# DRV8701E_V1_0.net
KiCad netlist of a schematic drawn in EasyEDA Pro
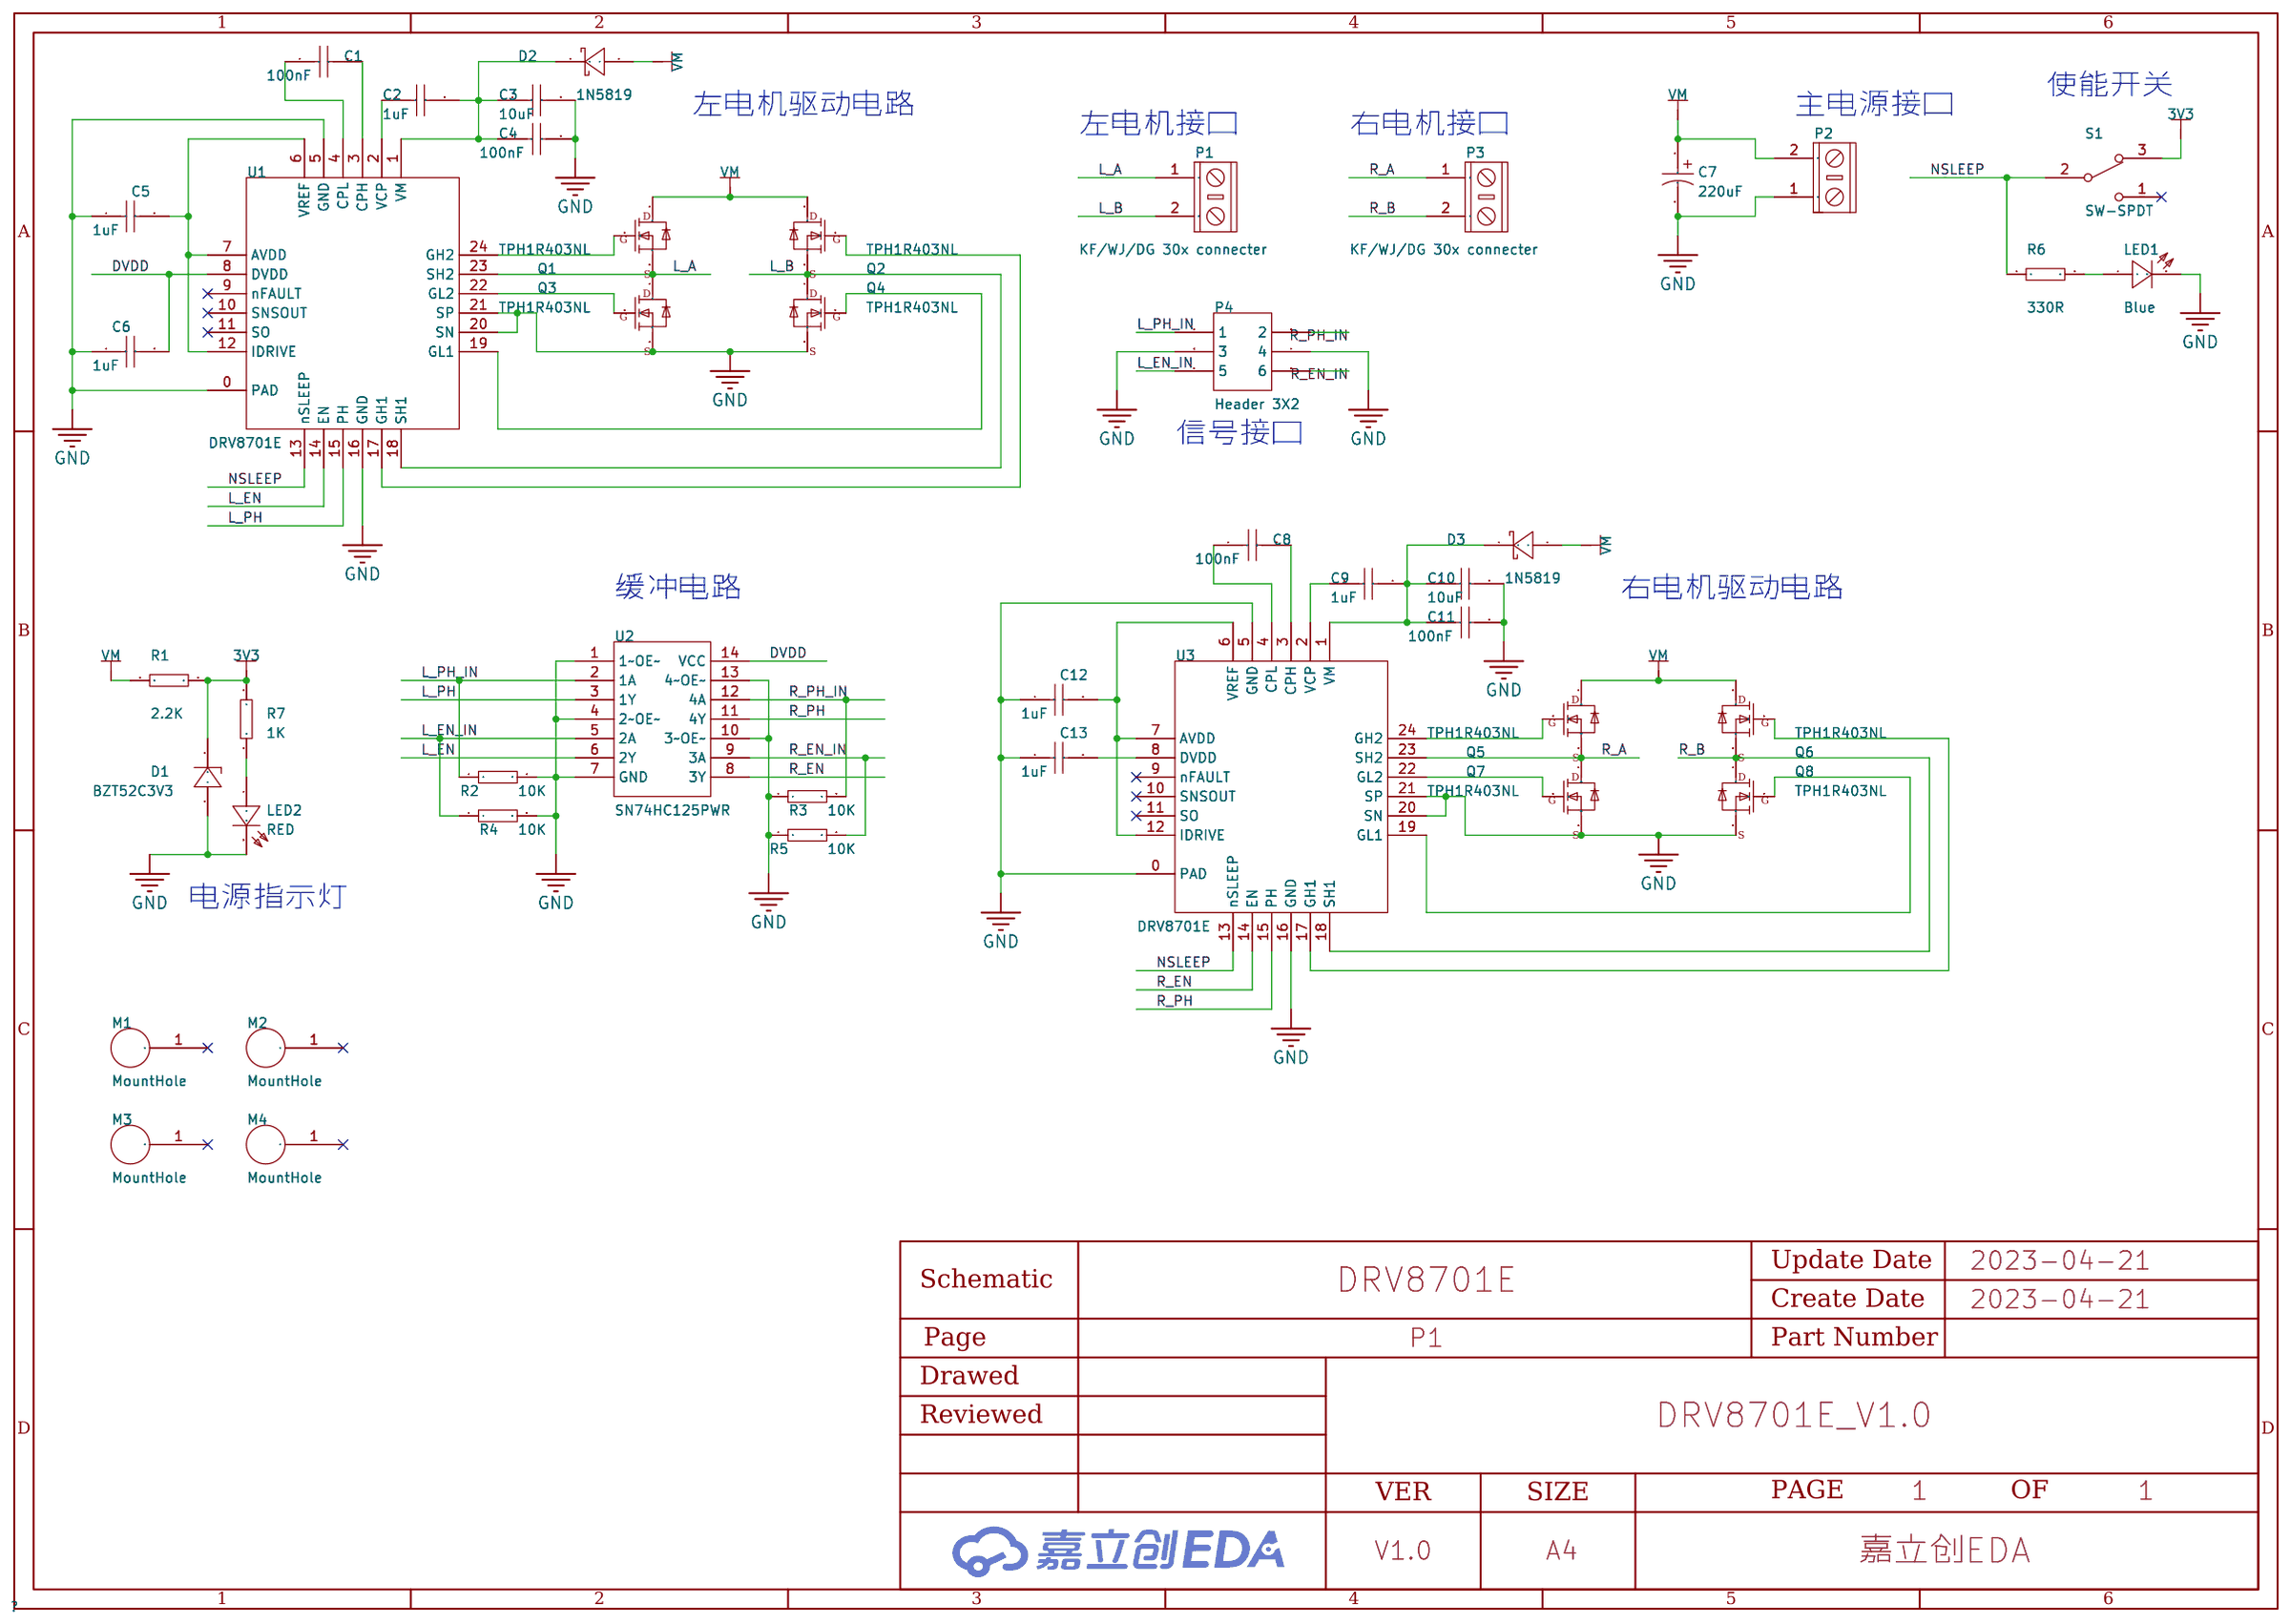
[diagram p0: schematic sheet]

(export (version "E")
  (design (tool "Eeschema 10.0.6"))
  (components
    (comp (ref "C1")
      (value "100nF")
      (footprint "easyedapro:CAPC1608[0603]S-N")
      (libsource (lib "easyedapro") (part "Cap-Chip_1"))
    )
    (comp (ref "C2")
      (value "1uF")
      (footprint "easyedapro:CAPC1608[0603]S-N")
      (libsource (lib "easyedapro") (part "Cap-Chip_2"))
    )
    (comp (ref "C3")
      (value "10uF")
      (footprint "easyedapro:CAPC2012[0805]S-N")
      (libsource (lib "easyedapro") (part "Cap-Chip"))
    )
    (comp (ref "C4")
      (value "100nF")
      (footprint "easyedapro:CAPC1608[0603]S-N")
      (libsource (lib "easyedapro") (part "Cap-Chip_1"))
    )
    (comp (ref "C5")
      (value "1uF")
      (footprint "easyedapro:CAPC1608[0603]S-N")
      (libsource (lib "easyedapro") (part "Cap-Chip_2"))
    )
    (comp (ref "C6")
      (value "1uF")
      (footprint "easyedapro:CAPC1608[0603]S-N")
      (libsource (lib "easyedapro") (part "Cap-Chip_2"))
    )
    (comp (ref "C7")
      (value "220uF")
      (footprint "easyedapro:CAPPR3.5-8X11.5")
      (libsource (lib "easyedapro") (part "Cap-Elect"))
    )
    (comp (ref "C8")
      (value "100nF")
      (footprint "easyedapro:CAPC1608[0603]S-N")
      (libsource (lib "easyedapro") (part "Cap-Chip_1"))
    )
    (comp (ref "C9")
      (value "1uF")
      (footprint "easyedapro:CAPC1608[0603]S-N")
      (libsource (lib "easyedapro") (part "Cap-Chip_2"))
    )
    (comp (ref "C10")
      (value "10uF")
      (footprint "easyedapro:CAPC2012[0805]S-N")
      (libsource (lib "easyedapro") (part "Cap-Chip"))
    )
    (comp (ref "C11")
      (value "100nF")
      (footprint "easyedapro:CAPC1608[0603]S-N")
      (libsource (lib "easyedapro") (part "Cap-Chip_1"))
    )
    (comp (ref "C12")
      (value "1uF")
      (footprint "easyedapro:CAPC1608[0603]S-N")
      (libsource (lib "easyedapro") (part "Cap-Chip_2"))
    )
    (comp (ref "C13")
      (value "1uF")
      (footprint "easyedapro:CAPC1608[0603]S-N")
      (libsource (lib "easyedapro") (part "Cap-Chip_2"))
    )
    (comp (ref "D1")
      (value "BZT52C3V3")
      (footprint "easyedapro:SOD-123-L")
      (libsource (lib "easyedapro") (part "Diode Zen"))
    )
    (comp (ref "D2")
      (value "1N5819")
      (footprint "easyedapro:SOD-123-L")
      (libsource (lib "easyedapro") (part "Diode Schottky"))
    )
    (comp (ref "D3")
      (value "1N5819")
      (footprint "easyedapro:SOD-123-L")
      (libsource (lib "easyedapro") (part "Diode Schottky"))
    )
    (comp (ref "LED1")
      (value "Blue")
      (footprint "easyedapro:LEDC1608(0603)")
      (libsource (lib "easyedapro") (part "LED Chip Blue"))
    )
    (comp (ref "LED2")
      (value "RED")
      (footprint "easyedapro:LEDC1608(0603)")
      (libsource (lib "easyedapro") (part "LED Chip Red"))
    )
    (comp (ref "M1")
      (value "MountHole")
      (footprint "easyedapro:M3-MountSlot")
      (libsource (lib "easyedapro") (part "MountHole"))
    )
    (comp (ref "M2")
      (value "MountHole")
      (footprint "easyedapro:M3-MountSlot")
      (libsource (lib "easyedapro") (part "MountHole"))
    )
    (comp (ref "M3")
      (value "MountHole")
      (footprint "easyedapro:M3-MountSlot")
      (libsource (lib "easyedapro") (part "MountHole"))
    )
    (comp (ref "M4")
      (value "MountHole")
      (footprint "easyedapro:M3-MountSlot")
      (libsource (lib "easyedapro") (part "MountHole"))
    )
    (comp (ref "P1")
      (value "KF/WJ/DG 30x connecter")
      (footprint "easyedapro:KF/WJ/DG 301-2p-5.0mm")
      (libsource (lib "easyedapro") (part "KF/WJ/DG 30x"))
    )
    (comp (ref "P2")
      (value "KF/WJ/DG 30x connecter")
      (footprint "easyedapro:KF/WJ/DG 301-2p-5.0mm")
      (libsource (lib "easyedapro") (part "KF/WJ/DG 30x"))
    )
    (comp (ref "P3")
      (value "KF/WJ/DG 30x connecter")
      (footprint "easyedapro:KF/WJ/DG 301-2p-5.0mm")
      (libsource (lib "easyedapro") (part "KF/WJ/DG 30x"))
    )
    (comp (ref "P4")
      (value "Header 3X2")
      (footprint "easyedapro:HDR2X3")
      (libsource (lib "easyedapro") (part "Header 3X2"))
    )
    (comp (ref "Q1")
      (value "TPH1R403NL")
      (footprint "easyedapro:DFN5x6")
      (libsource (lib "easyedapro") (part "TPH1R403NL"))
    )
    (comp (ref "Q2")
      (value "TPH1R403NL")
      (footprint "easyedapro:DFN5x6")
      (libsource (lib "easyedapro") (part "TPH1R403NL"))
    )
    (comp (ref "Q3")
      (value "TPH1R403NL")
      (footprint "easyedapro:DFN5x6")
      (libsource (lib "easyedapro") (part "TPH1R403NL"))
    )
    (comp (ref "Q4")
      (value "TPH1R403NL")
      (footprint "easyedapro:DFN5x6")
      (libsource (lib "easyedapro") (part "TPH1R403NL"))
    )
    (comp (ref "Q5")
      (value "TPH1R403NL")
      (footprint "easyedapro:DFN5x6")
      (libsource (lib "easyedapro") (part "TPH1R403NL"))
    )
    (comp (ref "Q6")
      (value "TPH1R403NL")
      (footprint "easyedapro:DFN5x6")
      (libsource (lib "easyedapro") (part "TPH1R403NL"))
    )
    (comp (ref "Q7")
      (value "TPH1R403NL")
      (footprint "easyedapro:DFN5x6")
      (libsource (lib "easyedapro") (part "TPH1R403NL"))
    )
    (comp (ref "Q8")
      (value "TPH1R403NL")
      (footprint "easyedapro:DFN5x6")
      (libsource (lib "easyedapro") (part "TPH1R403NL"))
    )
    (comp (ref "R1")
      (value "2.2K")
      (footprint "easyedapro:RESC1608[0603]S-N")
      (libsource (lib "easyedapro") (part "Res-Chip"))
    )
    (comp (ref "R2")
      (value "10K")
      (footprint "easyedapro:RESC1608[0603]S-N")
      (libsource (lib "easyedapro") (part "Res-Chip_1"))
    )
    (comp (ref "R3")
      (value "10K")
      (footprint "easyedapro:RESC1608[0603]S-N")
      (libsource (lib "easyedapro") (part "Res-Chip_1"))
    )
    (comp (ref "R4")
      (value "10K")
      (footprint "easyedapro:RESC1608[0603]S-N")
      (libsource (lib "easyedapro") (part "Res-Chip_1"))
    )
    (comp (ref "R5")
      (value "10K")
      (footprint "easyedapro:RESC1608[0603]S-N")
      (libsource (lib "easyedapro") (part "Res-Chip_1"))
    )
    (comp (ref "R6")
      (value "330R")
      (footprint "easyedapro:RESC1608[0603]S-N")
      (libsource (lib "easyedapro") (part "Res-Chip_3"))
    )
    (comp (ref "R7")
      (value "1K")
      (footprint "easyedapro:RESC1608[0603]S-N")
      (libsource (lib "easyedapro") (part "Res-Chip_2"))
    )
    (comp (ref "S1")
      (value "SW-SPDT")
      (footprint "easyedapro:SS12D10")
      (libsource (lib "easyedapro") (part "SW-SPDT"))
    )
    (comp (ref "U1")
      (value "DRV8701E")
      (footprint "easyedapro:QFN24-4x4")
      (libsource (lib "easyedapro") (part "DRV8701E"))
    )
    (comp (ref "U2")
      (value "SN74HC125PWR")
      (footprint "easyedapro:TSSOP-14")
      (libsource (lib "easyedapro") (part "SN74HC125PWR"))
    )
    (comp (ref "U3")
      (value "DRV8701E")
      (footprint "easyedapro:QFN24-4x4")
      (libsource (lib "easyedapro") (part "DRV8701E"))
    )
  )
  (nets
    (net (code "1") (name "/DVDD") (class "Default")
      (node (ref "C6") (pin "2") (pinfunction "2_2") (pintype "input"))
      (node (ref "U1") (pin "8") (pinfunction "DVDD_8") (pintype "input"))
      (node (ref "U2") (pin "14") (pinfunction "VCC_14") (pintype "input"))
    )
    (net (code "2") (name "/L_A") (class "Default")
      (node (ref "P1") (pin "1") (pinfunction "1_1") (pintype "input"))
      (node (ref "Q1") (pin "3") (pinfunction "S_3") (pintype "input"))
      (node (ref "Q3") (pin "1") (pinfunction "D_1") (pintype "input"))
      (node (ref "U1") (pin "23") (pinfunction "SH2_23") (pintype "input"))
    )
    (net (code "3") (name "/L_B") (class "Default")
      (node (ref "P1") (pin "2") (pinfunction "2_2") (pintype "input"))
      (node (ref "Q2") (pin "3") (pinfunction "S_3") (pintype "input"))
      (node (ref "Q4") (pin "1") (pinfunction "D_1") (pintype "input"))
      (node (ref "U1") (pin "18") (pinfunction "SH1_18") (pintype "input"))
    )
    (net (code "4") (name "/L_EN") (class "Default")
      (node (ref "U1") (pin "14") (pinfunction "EN_14") (pintype "input"))
      (node (ref "U2") (pin "6") (pinfunction "2Y_6") (pintype "input"))
    )
    (net (code "5") (name "/L_EN_IN") (class "Default")
      (node (ref "P4") (pin "5") (pinfunction "5_5") (pintype "input"))
      (node (ref "R4") (pin "1") (pinfunction "1_1") (pintype "input"))
      (node (ref "U2") (pin "5") (pinfunction "2A_5") (pintype "input"))
    )
    (net (code "6") (name "/L_PH") (class "Default")
      (node (ref "U1") (pin "15") (pinfunction "PH_15") (pintype "input"))
      (node (ref "U2") (pin "3") (pinfunction "1Y_3") (pintype "input"))
    )
    (net (code "7") (name "/L_PH_IN") (class "Default")
      (node (ref "P4") (pin "1") (pinfunction "1_1") (pintype "input"))
      (node (ref "R2") (pin "1") (pinfunction "1_1") (pintype "input"))
      (node (ref "U2") (pin "2") (pinfunction "1A_2") (pintype "input"))
    )
    (net (code "8") (name "/NSLEEP") (class "Default")
      (node (ref "R6") (pin "1") (pinfunction "1_1") (pintype "input"))
      (node (ref "S1") (pin "2") (pintype "input"))
      (node (ref "U1") (pin "13") (pinfunction "nSLEEP_13") (pintype "input"))
      (node (ref "U3") (pin "13") (pinfunction "nSLEEP_13") (pintype "input"))
    )
    (net (code "9") (name "/R_A") (class "Default")
      (node (ref "P3") (pin "1") (pinfunction "1_1") (pintype "input"))
      (node (ref "Q5") (pin "3") (pinfunction "S_3") (pintype "input"))
      (node (ref "Q7") (pin "1") (pinfunction "D_1") (pintype "input"))
      (node (ref "U3") (pin "23") (pinfunction "SH2_23") (pintype "input"))
    )
    (net (code "10") (name "/R_B") (class "Default")
      (node (ref "P3") (pin "2") (pinfunction "2_2") (pintype "input"))
      (node (ref "Q6") (pin "3") (pinfunction "S_3") (pintype "input"))
      (node (ref "Q8") (pin "1") (pinfunction "D_1") (pintype "input"))
      (node (ref "U3") (pin "18") (pinfunction "SH1_18") (pintype "input"))
    )
    (net (code "11") (name "/R_EN") (class "Default")
      (node (ref "U2") (pin "8") (pinfunction "3Y_8") (pintype "input"))
      (node (ref "U3") (pin "14") (pinfunction "EN_14") (pintype "input"))
    )
    (net (code "12") (name "/R_EN_IN") (class "Default")
      (node (ref "P4") (pin "6") (pinfunction "6_6") (pintype "input"))
      (node (ref "R5") (pin "2") (pinfunction "2_2") (pintype "input"))
      (node (ref "U2") (pin "9") (pinfunction "3A_9") (pintype "input"))
    )
    (net (code "13") (name "/R_PH") (class "Default")
      (node (ref "U2") (pin "11") (pinfunction "4Y_11") (pintype "input"))
      (node (ref "U3") (pin "15") (pinfunction "PH_15") (pintype "input"))
    )
    (net (code "14") (name "/R_PH_IN") (class "Default")
      (node (ref "P4") (pin "2") (pinfunction "2_2") (pintype "input"))
      (node (ref "R3") (pin "2") (pinfunction "2_2") (pintype "input"))
      (node (ref "U2") (pin "12") (pinfunction "4A_12") (pintype "input"))
    )
    (net (code "15") (name "3V3") (class "Default")
      (node (ref "D1") (pin "K") (pinfunction "K_K") (pintype "input"))
      (node (ref "R1") (pin "2") (pinfunction "2_2") (pintype "input"))
      (node (ref "R7") (pin "1") (pinfunction "1_1") (pintype "input"))
      (node (ref "S1") (pin "3") (pintype "input"))
    )
    (net (code "16") (name "GND") (class "Default")
      (node (ref "C10") (pin "2") (pinfunction "2_2") (pintype "input"))
      (node (ref "C11") (pin "2") (pinfunction "2_2") (pintype "input"))
      (node (ref "C12") (pin "1") (pinfunction "1_1") (pintype "input"))
      (node (ref "C13") (pin "1") (pinfunction "1_1") (pintype "input"))
      (node (ref "C3") (pin "2") (pinfunction "2_2") (pintype "input"))
      (node (ref "C4") (pin "2") (pinfunction "2_2") (pintype "input"))
      (node (ref "C5") (pin "1") (pinfunction "1_1") (pintype "input"))
      (node (ref "C6") (pin "1") (pinfunction "1_1") (pintype "input"))
      (node (ref "C7") (pin "2") (pinfunction "2_2") (pintype "input"))
      (node (ref "D1") (pin "A") (pinfunction "A_A") (pintype "input"))
      (node (ref "LED1") (pin "C") (pinfunction "C_C") (pintype "input"))
      (node (ref "LED2") (pin "C") (pinfunction "C_C") (pintype "input"))
      (node (ref "P2") (pin "1") (pinfunction "1_1") (pintype "input"))
      (node (ref "P4") (pin "3") (pinfunction "3_3") (pintype "input"))
      (node (ref "P4") (pin "4") (pinfunction "4_4") (pintype "input"))
      (node (ref "Q3") (pin "3") (pinfunction "S_3") (pintype "input"))
      (node (ref "Q4") (pin "3") (pinfunction "S_3") (pintype "input"))
      (node (ref "Q7") (pin "3") (pinfunction "S_3") (pintype "input"))
      (node (ref "Q8") (pin "3") (pinfunction "S_3") (pintype "input"))
      (node (ref "R2") (pin "2") (pinfunction "2_2") (pintype "input"))
      (node (ref "R3") (pin "1") (pinfunction "1_1") (pintype "input"))
      (node (ref "R4") (pin "2") (pinfunction "2_2") (pintype "input"))
      (node (ref "R5") (pin "1") (pinfunction "1_1") (pintype "input"))
      (node (ref "U1") (pin "0") (pinfunction "PAD_0") (pintype "input"))
      (node (ref "U1") (pin "16") (pinfunction "GND_16") (pintype "input"))
      (node (ref "U1") (pin "20") (pinfunction "SN_20") (pintype "input"))
      (node (ref "U1") (pin "21") (pinfunction "SP_21") (pintype "input"))
      (node (ref "U1") (pin "5") (pinfunction "GND_5") (pintype "input"))
      (node (ref "U2") (pin "1") (pinfunction "1~OE~_1") (pintype "input"))
      (node (ref "U2") (pin "10") (pinfunction "3~OE~_10") (pintype "input"))
      (node (ref "U2") (pin "13") (pinfunction "4~OE~_13") (pintype "input"))
      (node (ref "U2") (pin "4") (pinfunction "2~OE~_4") (pintype "input"))
      (node (ref "U2") (pin "7") (pinfunction "GND_7") (pintype "input"))
      (node (ref "U3") (pin "0") (pinfunction "PAD_0") (pintype "input"))
      (node (ref "U3") (pin "16") (pinfunction "GND_16") (pintype "input"))
      (node (ref "U3") (pin "20") (pinfunction "SN_20") (pintype "input"))
      (node (ref "U3") (pin "21") (pinfunction "SP_21") (pintype "input"))
      (node (ref "U3") (pin "5") (pinfunction "GND_5") (pintype "input"))
    )
    (net (code "17") (name "Net-(LED1-PadA)") (class "Default")
      (node (ref "LED1") (pin "A") (pinfunction "A_A") (pintype "input"))
      (node (ref "R6") (pin "2") (pinfunction "2_2") (pintype "input"))
    )
    (net (code "18") (name "Net-(LED2-PadA)") (class "Default")
      (node (ref "LED2") (pin "A") (pinfunction "A_A") (pintype "input"))
      (node (ref "R7") (pin "2") (pinfunction "2_2") (pintype "input"))
    )
    (net (code "19") (name "Net-(Q1-G)") (class "Default")
      (node (ref "Q1") (pin "2") (pinfunction "G_2") (pintype "input"))
      (node (ref "U1") (pin "24") (pinfunction "GH2_24") (pintype "input"))
    )
    (net (code "20") (name "Net-(Q2-G)") (class "Default")
      (node (ref "Q2") (pin "2") (pinfunction "G_2") (pintype "input"))
      (node (ref "U1") (pin "17") (pinfunction "GH1_17") (pintype "input"))
    )
    (net (code "21") (name "Net-(Q3-G)") (class "Default")
      (node (ref "Q3") (pin "2") (pinfunction "G_2") (pintype "input"))
      (node (ref "U1") (pin "22") (pinfunction "GL2_22") (pintype "input"))
    )
    (net (code "22") (name "Net-(Q4-G)") (class "Default")
      (node (ref "Q4") (pin "2") (pinfunction "G_2") (pintype "input"))
      (node (ref "U1") (pin "19") (pinfunction "GL1_19") (pintype "input"))
    )
    (net (code "23") (name "Net-(Q5-G)") (class "Default")
      (node (ref "Q5") (pin "2") (pinfunction "G_2") (pintype "input"))
      (node (ref "U3") (pin "24") (pinfunction "GH2_24") (pintype "input"))
    )
    (net (code "24") (name "Net-(Q6-G)") (class "Default")
      (node (ref "Q6") (pin "2") (pinfunction "G_2") (pintype "input"))
      (node (ref "U3") (pin "17") (pinfunction "GH1_17") (pintype "input"))
    )
    (net (code "25") (name "Net-(Q7-G)") (class "Default")
      (node (ref "Q7") (pin "2") (pinfunction "G_2") (pintype "input"))
      (node (ref "U3") (pin "22") (pinfunction "GL2_22") (pintype "input"))
    )
    (net (code "26") (name "Net-(Q8-G)") (class "Default")
      (node (ref "Q8") (pin "2") (pinfunction "G_2") (pintype "input"))
      (node (ref "U3") (pin "19") (pinfunction "GL1_19") (pintype "input"))
    )
    (net (code "27") (name "Net-(U1-AVDD)") (class "Default")
      (node (ref "C5") (pin "2") (pinfunction "2_2") (pintype "input"))
      (node (ref "U1") (pin "12") (pinfunction "IDRIVE_12") (pintype "input"))
      (node (ref "U1") (pin "6") (pinfunction "VREF_6") (pintype "input"))
      (node (ref "U1") (pin "7") (pinfunction "AVDD_7") (pintype "input"))
    )
    (net (code "28") (name "Net-(U1-CPH)") (class "Default")
      (node (ref "C1") (pin "2") (pinfunction "2_2") (pintype "input"))
      (node (ref "U1") (pin "3") (pinfunction "CPH_3") (pintype "input"))
    )
    (net (code "29") (name "Net-(U1-CPL)") (class "Default")
      (node (ref "C1") (pin "1") (pinfunction "1_1") (pintype "input"))
      (node (ref "U1") (pin "4") (pinfunction "CPL_4") (pintype "input"))
    )
    (net (code "30") (name "Net-(U1-VCP)") (class "Default")
      (node (ref "C2") (pin "1") (pinfunction "1_1") (pintype "input"))
      (node (ref "U1") (pin "2") (pinfunction "VCP_2") (pintype "input"))
    )
    (net (code "31") (name "Net-(U1-VM)") (class "Default")
      (node (ref "C2") (pin "2") (pinfunction "2_2") (pintype "input"))
      (node (ref "C3") (pin "1") (pinfunction "1_1") (pintype "input"))
      (node (ref "C4") (pin "1") (pinfunction "1_1") (pintype "input"))
      (node (ref "D2") (pin "K") (pinfunction "K_K") (pintype "input"))
      (node (ref "U1") (pin "1") (pinfunction "VM_1") (pintype "input"))
    )
    (net (code "32") (name "Net-(U3-AVDD)") (class "Default")
      (node (ref "C12") (pin "2") (pinfunction "2_2") (pintype "input"))
      (node (ref "U3") (pin "12") (pinfunction "IDRIVE_12") (pintype "input"))
      (node (ref "U3") (pin "6") (pinfunction "VREF_6") (pintype "input"))
      (node (ref "U3") (pin "7") (pinfunction "AVDD_7") (pintype "input"))
    )
    (net (code "33") (name "Net-(U3-CPH)") (class "Default")
      (node (ref "C8") (pin "2") (pinfunction "2_2") (pintype "input"))
      (node (ref "U3") (pin "3") (pinfunction "CPH_3") (pintype "input"))
    )
    (net (code "34") (name "Net-(U3-CPL)") (class "Default")
      (node (ref "C8") (pin "1") (pinfunction "1_1") (pintype "input"))
      (node (ref "U3") (pin "4") (pinfunction "CPL_4") (pintype "input"))
    )
    (net (code "35") (name "Net-(U3-DVDD)") (class "Default")
      (node (ref "C13") (pin "2") (pinfunction "2_2") (pintype "input"))
      (node (ref "U3") (pin "8") (pinfunction "DVDD_8") (pintype "input"))
    )
    (net (code "36") (name "Net-(U3-VCP)") (class "Default")
      (node (ref "C9") (pin "1") (pinfunction "1_1") (pintype "input"))
      (node (ref "U3") (pin "2") (pinfunction "VCP_2") (pintype "input"))
    )
    (net (code "37") (name "Net-(U3-VM)") (class "Default")
      (node (ref "C10") (pin "1") (pinfunction "1_1") (pintype "input"))
      (node (ref "C11") (pin "1") (pinfunction "1_1") (pintype "input"))
      (node (ref "C9") (pin "2") (pinfunction "2_2") (pintype "input"))
      (node (ref "D3") (pin "K") (pinfunction "K_K") (pintype "input"))
      (node (ref "U3") (pin "1") (pinfunction "VM_1") (pintype "input"))
    )
    (net (code "38") (name "VM") (class "Default")
      (node (ref "C7") (pin "1") (pinfunction "1_1") (pintype "input"))
      (node (ref "D2") (pin "A") (pinfunction "A_A") (pintype "input"))
      (node (ref "D3") (pin "A") (pinfunction "A_A") (pintype "input"))
      (node (ref "P2") (pin "2") (pinfunction "2_2") (pintype "input"))
      (node (ref "Q1") (pin "1") (pinfunction "D_1") (pintype "input"))
      (node (ref "Q2") (pin "1") (pinfunction "D_1") (pintype "input"))
      (node (ref "Q5") (pin "1") (pinfunction "D_1") (pintype "input"))
      (node (ref "Q6") (pin "1") (pinfunction "D_1") (pintype "input"))
      (node (ref "R1") (pin "1") (pinfunction "1_1") (pintype "input"))
    )
    (net (code "39") (name "unconnected-(M1-Pad1)") (class "Default")
      (node (ref "M1") (pin "1") (pinfunction "1_1") (pintype "input+no_connect"))
    )
    (net (code "40") (name "unconnected-(M2-Pad1)") (class "Default")
      (node (ref "M2") (pin "1") (pinfunction "1_1") (pintype "input+no_connect"))
    )
    (net (code "41") (name "unconnected-(M3-Pad1)") (class "Default")
      (node (ref "M3") (pin "1") (pinfunction "1_1") (pintype "input+no_connect"))
    )
    (net (code "42") (name "unconnected-(M4-Pad1)") (class "Default")
      (node (ref "M4") (pin "1") (pinfunction "1_1") (pintype "input+no_connect"))
    )
    (net (code "43") (name "unconnected-(S1-Pad1)") (class "Default")
      (node (ref "S1") (pin "1") (pintype "input+no_connect"))
    )
    (net (code "44") (name "unconnected-(U1-SNSOUT-Pad10)") (class "Default")
      (node (ref "U1") (pin "10") (pinfunction "SNSOUT_10") (pintype "input+no_connect"))
    )
    (net (code "45") (name "unconnected-(U1-SO-Pad11)") (class "Default")
      (node (ref "U1") (pin "11") (pinfunction "SO_11") (pintype "input+no_connect"))
    )
    (net (code "46") (name "unconnected-(U1-nFAULT-Pad9)") (class "Default")
      (node (ref "U1") (pin "9") (pinfunction "nFAULT_9") (pintype "input+no_connect"))
    )
    (net (code "47") (name "unconnected-(U3-SNSOUT-Pad10)") (class "Default")
      (node (ref "U3") (pin "10") (pinfunction "SNSOUT_10") (pintype "input+no_connect"))
    )
    (net (code "48") (name "unconnected-(U3-SO-Pad11)") (class "Default")
      (node (ref "U3") (pin "11") (pinfunction "SO_11") (pintype "input+no_connect"))
    )
    (net (code "49") (name "unconnected-(U3-nFAULT-Pad9)") (class "Default")
      (node (ref "U3") (pin "9") (pinfunction "nFAULT_9") (pintype "input+no_connect"))
    )
  )
)
